# VCA_2.net
KiCad netlist of a schematic drawn in Altium Designer
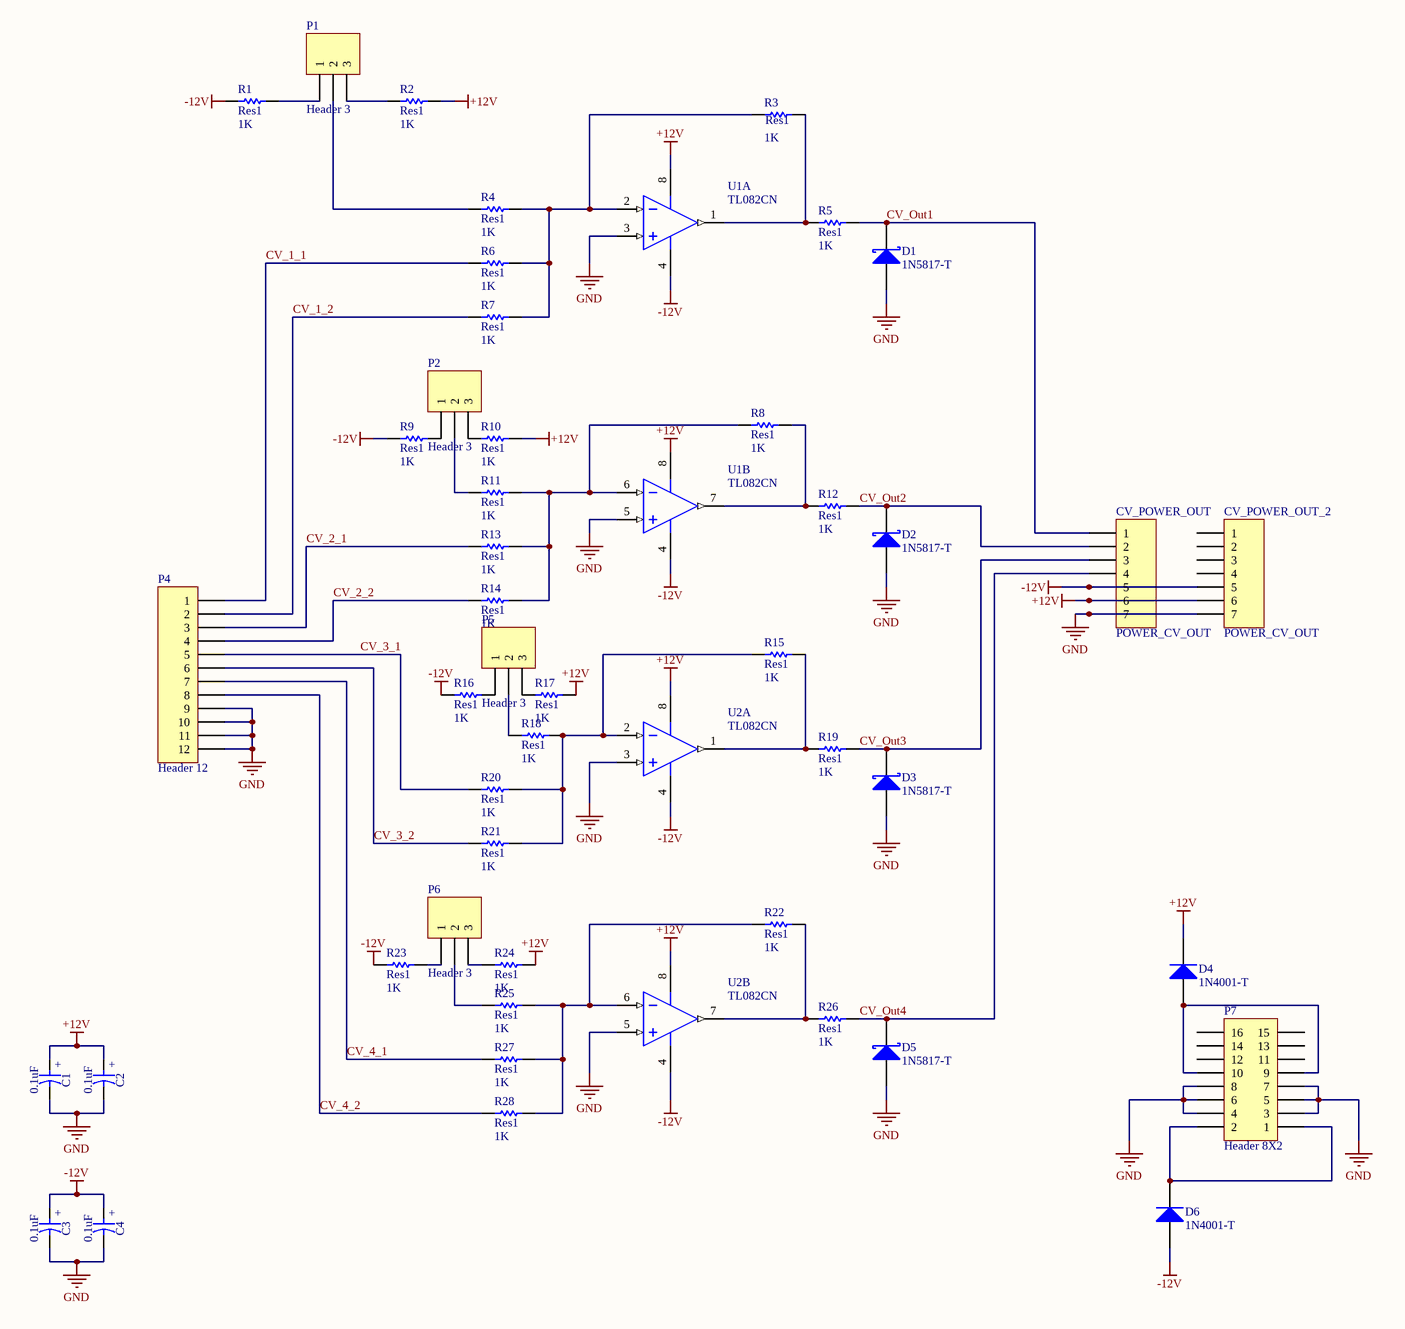
[diagram p0: VCA_2.SchDoc]

(export (version "E")
  (design (tool "Eeschema 10.0.6"))
  (components
    (comp (ref "C1")
      (value "0.1uF")
      (footprint "CAPPRB508-450x850")
      (description "Polarised capacitor")
      (fields
        (field (name "PART NUMBER") "CTEB_0.1UF_35V_10%_508-450X850")
        (field (name "VOLTAGE") "35V")
        (field (name "AUTHOR") "CERN DEM JLC")
      )
      (libsource (lib "Capacitors") (part "Capacitor - polarized"))
    )
    (comp (ref "C2")
      (value "0.1uF")
      (footprint "CAPPRB508-450x850")
      (description "Polarised capacitor")
      (fields
        (field (name "PART NUMBER") "CTEB_0.1UF_35V_10%_508-450X850")
        (field (name "VOLTAGE") "35V")
        (field (name "AUTHOR") "CERN DEM JLC")
      )
      (libsource (lib "Capacitors") (part "Capacitor - polarized"))
    )
    (comp (ref "C3")
      (value "0.1uF")
      (footprint "CAPPRB508-450x850")
      (description "Polarised capacitor")
      (fields
        (field (name "PART NUMBER") "CTEB_0.1UF_35V_10%_508-450X850")
        (field (name "VOLTAGE") "35V")
        (field (name "AUTHOR") "CERN DEM JLC")
      )
      (libsource (lib "Capacitors") (part "Capacitor - polarized"))
    )
    (comp (ref "C4")
      (value "0.1uF")
      (footprint "CAPPRB508-450x850")
      (description "Polarised capacitor")
      (fields
        (field (name "PART NUMBER") "CTEB_0.1UF_35V_10%_508-450X850")
        (field (name "VOLTAGE") "35V")
        (field (name "AUTHOR") "CERN DEM JLC")
      )
      (libsource (lib "Capacitors") (part "Capacitor - polarized"))
    )
    (comp (ref "CV_POWER_OUT")
      (value "POWER_CV_OUT")
      (footprint "HDR1X7")
      (description "Header, 7-Pin")
      (fields (field (name "PUBLISHER") "Altium Limited"))
      (libsource (lib "Miscellaneous Connectors") (part "Header 7"))
    )
    (comp (ref "CV_POWER_OUT_2")
      (value "POWER_CV_OUT")
      (footprint "HDR1X7")
      (description "Header, 7-Pin")
      (fields (field (name "PUBLISHER") "Altium Limited"))
      (libsource (lib "Miscellaneous Connectors") (part "Header 7"))
    )
    (comp (ref "D1")
      (value "1N5817-T")
      (footprint "DIOD-DO-41-P-2")
      (description "Schottky Barrier Rectifier, 1 A, 20 V, -65 to 125 degC, 2-Pin DO-41, RoHS, Tape and Reel")
      (fields (field (name "MANUFACTURER") "DiodesIncorporated"))
      (libsource (lib "Altium Content Vault") (part "DSKY-AK-2"))
    )
    (comp (ref "D2")
      (value "1N5817-T")
      (footprint "DIOD-DO-41-P-2")
      (description "Schottky Barrier Rectifier, 1 A, 20 V, -65 to 125 degC, 2-Pin DO-41, RoHS, Tape and Reel")
      (fields (field (name "MANUFACTURER") "DiodesIncorporated"))
      (libsource (lib "Altium Content Vault") (part "DSKY-AK-2"))
    )
    (comp (ref "D3")
      (value "1N5817-T")
      (footprint "DIOD-DO-41-P-2")
      (description "Schottky Barrier Rectifier, 1 A, 20 V, -65 to 125 degC, 2-Pin DO-41, RoHS, Tape and Reel")
      (fields (field (name "MANUFACTURER") "DiodesIncorporated"))
      (libsource (lib "Altium Content Vault") (part "DSKY-AK-2"))
    )
    (comp (ref "D4")
      (value "1N4001-T")
      (footprint "DIOD-DO-41-P-2_V")
      (description "1.0 A Rectifier, 15 pF, 50 V, -65 to 150 degC, 2-Pin DO-41 Plastic, RoHS, Tape and Reel")
      (fields (field (name "MANUFACTURER") "Diodes Inc"))
      (libsource (lib "Altium Content Vault") (part "DIOD-D-A1K2-2"))
    )
    (comp (ref "D5")
      (value "1N5817-T")
      (footprint "DIOD-DO-41-P-2")
      (description "Schottky Barrier Rectifier, 1 A, 20 V, -65 to 125 degC, 2-Pin DO-41, RoHS, Tape and Reel")
      (fields (field (name "MANUFACTURER") "DiodesIncorporated"))
      (libsource (lib "Altium Content Vault") (part "DSKY-AK-2"))
    )
    (comp (ref "D6")
      (value "1N4001-T")
      (footprint "DIOD-DO-41-P-2_V")
      (description "1.0 A Rectifier, 15 pF, 50 V, -65 to 150 degC, 2-Pin DO-41 Plastic, RoHS, Tape and Reel")
      (fields (field (name "MANUFACTURER") "Diodes Inc"))
      (libsource (lib "Altium Content Vault") (part "DIOD-D-A1K2-2"))
    )
    (comp (ref "P1")
      (value "Header 3")
      (footprint "HDR1X3")
      (description "Header, 3-Pin")
      (fields (field (name "PUBLISHER") "Altium Limited"))
      (libsource (lib "Miscellaneous Connectors") (part "Header 3"))
    )
    (comp (ref "P2")
      (value "Header 3")
      (footprint "HDR1X3")
      (description "Header, 3-Pin")
      (fields (field (name "PUBLISHER") "Altium Limited"))
      (libsource (lib "Miscellaneous Connectors") (part "Header 3"))
    )
    (comp (ref "P4")
      (value "Header 12")
      (footprint "HDR1X12")
      (description "Header, 12-Pin")
      (fields (field (name "PUBLISHER") "Altium Limited"))
      (libsource (lib "Miscellaneous Connectors") (part "Header 12"))
    )
    (comp (ref "P5")
      (value "Header 3")
      (footprint "HDR1X3")
      (description "Header, 3-Pin")
      (fields (field (name "PUBLISHER") "Altium Limited"))
      (libsource (lib "Miscellaneous Connectors") (part "Header 3"))
    )
    (comp (ref "P6")
      (value "Header 3")
      (footprint "HDR1X3")
      (description "Header, 3-Pin")
      (fields (field (name "PUBLISHER") "Altium Limited"))
      (libsource (lib "Miscellaneous Connectors") (part "Header 3"))
    )
    (comp (ref "P7")
      (value "Header 8X2")
      (footprint "HDR2X8")
      (description "Header, 8-Pin, Dual row")
      (fields (field (name "PUBLISHER") "Altium Limited"))
      (libsource (lib "Miscellaneous Connectors") (part "Header 8X2"))
    )
    (comp (ref "R1")
      (value "Res1")
      (footprint "AXIAL-0.3")
      (description "Resistor")
      (fields (field (name "ALTIUM_VALUE") "1K") (field (name "PUBLISHER") "Altium Limited"))
      (libsource (lib "Miscellaneous Devices") (part "Res1"))
    )
    (comp (ref "R2")
      (value "Res1")
      (footprint "AXIAL-0.3")
      (description "Resistor")
      (fields (field (name "ALTIUM_VALUE") "1K") (field (name "PUBLISHER") "Altium Limited"))
      (libsource (lib "Miscellaneous Devices") (part "Res1"))
    )
    (comp (ref "R3")
      (value "Res1")
      (footprint "AXIAL-0.3")
      (description "Resistor")
      (fields (field (name "ALTIUM_VALUE") "1K") (field (name "PUBLISHER") "Altium Limited"))
      (libsource (lib "Miscellaneous Devices") (part "Res1"))
    )
    (comp (ref "R4")
      (value "Res1")
      (footprint "AXIAL-0.3")
      (description "Resistor")
      (fields (field (name "ALTIUM_VALUE") "1K") (field (name "PUBLISHER") "Altium Limited"))
      (libsource (lib "Miscellaneous Devices") (part "Res1"))
    )
    (comp (ref "R5")
      (value "Res1")
      (footprint "AXIAL-0.3")
      (description "Resistor")
      (fields (field (name "ALTIUM_VALUE") "1K") (field (name "PUBLISHER") "Altium Limited"))
      (libsource (lib "Miscellaneous Devices") (part "Res1"))
    )
    (comp (ref "R6")
      (value "Res1")
      (footprint "AXIAL-0.3")
      (description "Resistor")
      (fields (field (name "ALTIUM_VALUE") "1K") (field (name "PUBLISHER") "Altium Limited"))
      (libsource (lib "Miscellaneous Devices") (part "Res1"))
    )
    (comp (ref "R7")
      (value "Res1")
      (footprint "AXIAL-0.3")
      (description "Resistor")
      (fields (field (name "ALTIUM_VALUE") "1K") (field (name "PUBLISHER") "Altium Limited"))
      (libsource (lib "Miscellaneous Devices") (part "Res1"))
    )
    (comp (ref "R8")
      (value "Res1")
      (footprint "AXIAL-0.3")
      (description "Resistor")
      (fields (field (name "ALTIUM_VALUE") "1K") (field (name "PUBLISHER") "Altium Limited"))
      (libsource (lib "Miscellaneous Devices") (part "Res1"))
    )
    (comp (ref "R9")
      (value "Res1")
      (footprint "AXIAL-0.3")
      (description "Resistor")
      (fields (field (name "ALTIUM_VALUE") "1K") (field (name "PUBLISHER") "Altium Limited"))
      (libsource (lib "Miscellaneous Devices") (part "Res1"))
    )
    (comp (ref "R10")
      (value "Res1")
      (footprint "AXIAL-0.3")
      (description "Resistor")
      (fields (field (name "ALTIUM_VALUE") "1K") (field (name "PUBLISHER") "Altium Limited"))
      (libsource (lib "Miscellaneous Devices") (part "Res1"))
    )
    (comp (ref "R11")
      (value "Res1")
      (footprint "AXIAL-0.3")
      (description "Resistor")
      (fields (field (name "ALTIUM_VALUE") "1K") (field (name "PUBLISHER") "Altium Limited"))
      (libsource (lib "Miscellaneous Devices") (part "Res1"))
    )
    (comp (ref "R12")
      (value "Res1")
      (footprint "AXIAL-0.3")
      (description "Resistor")
      (fields (field (name "ALTIUM_VALUE") "1K") (field (name "PUBLISHER") "Altium Limited"))
      (libsource (lib "Miscellaneous Devices") (part "Res1"))
    )
    (comp (ref "R13")
      (value "Res1")
      (footprint "AXIAL-0.3")
      (description "Resistor")
      (fields (field (name "ALTIUM_VALUE") "1K") (field (name "PUBLISHER") "Altium Limited"))
      (libsource (lib "Miscellaneous Devices") (part "Res1"))
    )
    (comp (ref "R14")
      (value "Res1")
      (footprint "AXIAL-0.3")
      (description "Resistor")
      (fields (field (name "ALTIUM_VALUE") "1K") (field (name "PUBLISHER") "Altium Limited"))
      (libsource (lib "Miscellaneous Devices") (part "Res1"))
    )
    (comp (ref "R15")
      (value "Res1")
      (footprint "AXIAL-0.3")
      (description "Resistor")
      (fields (field (name "ALTIUM_VALUE") "1K") (field (name "PUBLISHER") "Altium Limited"))
      (libsource (lib "Miscellaneous Devices") (part "Res1"))
    )
    (comp (ref "R16")
      (value "Res1")
      (footprint "AXIAL-0.3")
      (description "Resistor")
      (fields (field (name "ALTIUM_VALUE") "1K") (field (name "PUBLISHER") "Altium Limited"))
      (libsource (lib "Miscellaneous Devices") (part "Res1"))
    )
    (comp (ref "R17")
      (value "Res1")
      (footprint "AXIAL-0.3")
      (description "Resistor")
      (fields (field (name "ALTIUM_VALUE") "1K") (field (name "PUBLISHER") "Altium Limited"))
      (libsource (lib "Miscellaneous Devices") (part "Res1"))
    )
    (comp (ref "R18")
      (value "Res1")
      (footprint "AXIAL-0.3")
      (description "Resistor")
      (fields (field (name "ALTIUM_VALUE") "1K") (field (name "PUBLISHER") "Altium Limited"))
      (libsource (lib "Miscellaneous Devices") (part "Res1"))
    )
    (comp (ref "R19")
      (value "Res1")
      (footprint "AXIAL-0.3")
      (description "Resistor")
      (fields (field (name "ALTIUM_VALUE") "1K") (field (name "PUBLISHER") "Altium Limited"))
      (libsource (lib "Miscellaneous Devices") (part "Res1"))
    )
    (comp (ref "R20")
      (value "Res1")
      (footprint "AXIAL-0.3")
      (description "Resistor")
      (fields (field (name "ALTIUM_VALUE") "1K") (field (name "PUBLISHER") "Altium Limited"))
      (libsource (lib "Miscellaneous Devices") (part "Res1"))
    )
    (comp (ref "R21")
      (value "Res1")
      (footprint "AXIAL-0.3")
      (description "Resistor")
      (fields (field (name "ALTIUM_VALUE") "1K") (field (name "PUBLISHER") "Altium Limited"))
      (libsource (lib "Miscellaneous Devices") (part "Res1"))
    )
    (comp (ref "R22")
      (value "Res1")
      (footprint "AXIAL-0.3")
      (description "Resistor")
      (fields (field (name "ALTIUM_VALUE") "1K") (field (name "PUBLISHER") "Altium Limited"))
      (libsource (lib "Miscellaneous Devices") (part "Res1"))
    )
    (comp (ref "R23")
      (value "Res1")
      (footprint "AXIAL-0.3")
      (description "Resistor")
      (fields (field (name "ALTIUM_VALUE") "1K") (field (name "PUBLISHER") "Altium Limited"))
      (libsource (lib "Miscellaneous Devices") (part "Res1"))
    )
    (comp (ref "R24")
      (value "Res1")
      (footprint "AXIAL-0.3")
      (description "Resistor")
      (fields (field (name "ALTIUM_VALUE") "1K") (field (name "PUBLISHER") "Altium Limited"))
      (libsource (lib "Miscellaneous Devices") (part "Res1"))
    )
    (comp (ref "R25")
      (value "Res1")
      (footprint "AXIAL-0.3")
      (description "Resistor")
      (fields (field (name "ALTIUM_VALUE") "1K") (field (name "PUBLISHER") "Altium Limited"))
      (libsource (lib "Miscellaneous Devices") (part "Res1"))
    )
    (comp (ref "R26")
      (value "Res1")
      (footprint "AXIAL-0.3")
      (description "Resistor")
      (fields (field (name "ALTIUM_VALUE") "1K") (field (name "PUBLISHER") "Altium Limited"))
      (libsource (lib "Miscellaneous Devices") (part "Res1"))
    )
    (comp (ref "R27")
      (value "Res1")
      (footprint "AXIAL-0.3")
      (description "Resistor")
      (fields (field (name "ALTIUM_VALUE") "1K") (field (name "PUBLISHER") "Altium Limited"))
      (libsource (lib "Miscellaneous Devices") (part "Res1"))
    )
    (comp (ref "R28")
      (value "Res1")
      (footprint "AXIAL-0.3")
      (description "Resistor")
      (fields (field (name "ALTIUM_VALUE") "1K") (field (name "PUBLISHER") "Altium Limited"))
      (libsource (lib "Miscellaneous Devices") (part "Res1"))
    )
    (comp (ref "U1")
      (value "TL082CN")
      (footprint "STM-N8")
      (fields (field (name "MANUFACTURER") "STMicroelectronics"))
      (libsource (lib "Altium Content Vault") (part "STM-TL082-N8"))
    )
    (comp (ref "U2")
      (value "TL082CN")
      (footprint "STM-N8")
      (fields (field (name "MANUFACTURER") "STMicroelectronics"))
      (libsource (lib "Altium Content Vault") (part "STM-TL082-N8"))
    )
  )
  (nets
    (net (code "1") (name "+12V") (class "Default")
      (node (ref "C1") (pin "1") (pinfunction "1_1") (pintype "passive"))
      (node (ref "C2") (pin "1") (pinfunction "1_1") (pintype "passive"))
      (node (ref "CV_POWER_OUT") (pin "6") (pinfunction "6_6") (pintype "passive"))
      (node (ref "CV_POWER_OUT_2") (pin "6") (pinfunction "6_6") (pintype "passive"))
      (node (ref "D4") (pin "2") (pinfunction "K_2") (pintype "passive"))
      (node (ref "R10") (pin "2") (pinfunction "2_2") (pintype "passive"))
      (node (ref "R17") (pin "2") (pinfunction "2_2") (pintype "passive"))
      (node (ref "R2") (pin "2") (pinfunction "2_2") (pintype "passive"))
      (node (ref "R24") (pin "2") (pinfunction "2_2") (pintype "passive"))
      (node (ref "U1") (pin "8") (pinfunction "VCC+_8") (pintype "power_in"))
      (node (ref "U2") (pin "8") (pinfunction "VCC+_8") (pintype "power_in"))
    )
    (net (code "2") (name "-12V") (class "Default")
      (node (ref "C3") (pin "1") (pinfunction "1_1") (pintype "passive"))
      (node (ref "C4") (pin "1") (pinfunction "1_1") (pintype "passive"))
      (node (ref "CV_POWER_OUT") (pin "5") (pinfunction "5_5") (pintype "passive"))
      (node (ref "CV_POWER_OUT_2") (pin "5") (pinfunction "5_5") (pintype "passive"))
      (node (ref "D6") (pin "1") (pinfunction "A_1") (pintype "passive"))
      (node (ref "R1") (pin "1") (pinfunction "1_1") (pintype "passive"))
      (node (ref "R16") (pin "1") (pinfunction "1_1") (pintype "passive"))
      (node (ref "R23") (pin "1") (pinfunction "1_1") (pintype "passive"))
      (node (ref "R9") (pin "1") (pinfunction "1_1") (pintype "passive"))
      (node (ref "U1") (pin "4") (pinfunction "VCC-_4") (pintype "power_in"))
      (node (ref "U2") (pin "4") (pinfunction "VCC-_4") (pintype "power_in"))
    )
    (net (code "3") (name "/CV_1_1") (class "Default")
      (node (ref "P4") (pin "1") (pinfunction "1_1") (pintype "passive"))
      (node (ref "R6") (pin "1") (pinfunction "1_1") (pintype "passive"))
    )
    (net (code "4") (name "/CV_1_2") (class "Default")
      (node (ref "P4") (pin "2") (pinfunction "2_2") (pintype "passive"))
      (node (ref "R7") (pin "1") (pinfunction "1_1") (pintype "passive"))
    )
    (net (code "5") (name "/CV_2_1") (class "Default")
      (node (ref "P4") (pin "3") (pinfunction "3_3") (pintype "passive"))
      (node (ref "R13") (pin "1") (pinfunction "1_1") (pintype "passive"))
    )
    (net (code "6") (name "/CV_2_2") (class "Default")
      (node (ref "P4") (pin "4") (pinfunction "4_4") (pintype "passive"))
      (node (ref "R14") (pin "1") (pinfunction "1_1") (pintype "passive"))
    )
    (net (code "7") (name "/CV_3_1") (class "Default")
      (node (ref "P4") (pin "5") (pinfunction "5_5") (pintype "passive"))
      (node (ref "R20") (pin "1") (pinfunction "1_1") (pintype "passive"))
    )
    (net (code "8") (name "/CV_3_2") (class "Default")
      (node (ref "P4") (pin "6") (pinfunction "6_6") (pintype "passive"))
      (node (ref "R21") (pin "1") (pinfunction "1_1") (pintype "passive"))
    )
    (net (code "9") (name "/CV_4_1") (class "Default")
      (node (ref "P4") (pin "7") (pinfunction "7_7") (pintype "passive"))
      (node (ref "R27") (pin "1") (pinfunction "1_1") (pintype "passive"))
    )
    (net (code "10") (name "/CV_4_2") (class "Default")
      (node (ref "P4") (pin "8") (pinfunction "8_8") (pintype "passive"))
      (node (ref "R28") (pin "1") (pinfunction "1_1") (pintype "passive"))
    )
    (net (code "11") (name "/CV_Out1") (class "Default")
      (node (ref "CV_POWER_OUT") (pin "1") (pinfunction "1_1") (pintype "passive"))
      (node (ref "D1") (pin "2") (pinfunction "K_2") (pintype "passive"))
      (node (ref "R5") (pin "2") (pinfunction "2_2") (pintype "passive"))
    )
    (net (code "12") (name "/CV_Out2") (class "Default")
      (node (ref "CV_POWER_OUT") (pin "2") (pinfunction "2_2") (pintype "passive"))
      (node (ref "D2") (pin "2") (pinfunction "K_2") (pintype "passive"))
      (node (ref "R12") (pin "2") (pinfunction "2_2") (pintype "passive"))
    )
    (net (code "13") (name "/CV_Out3") (class "Default")
      (node (ref "CV_POWER_OUT") (pin "3") (pinfunction "3_3") (pintype "passive"))
      (node (ref "D3") (pin "2") (pinfunction "K_2") (pintype "passive"))
      (node (ref "R19") (pin "2") (pinfunction "2_2") (pintype "passive"))
    )
    (net (code "14") (name "/CV_Out4") (class "Default")
      (node (ref "CV_POWER_OUT") (pin "4") (pinfunction "4_4") (pintype "passive"))
      (node (ref "D5") (pin "2") (pinfunction "K_2") (pintype "passive"))
      (node (ref "R26") (pin "2") (pinfunction "2_2") (pintype "passive"))
    )
    (net (code "15") (name "GND") (class "Default")
      (node (ref "C1") (pin "2") (pinfunction "2_2") (pintype "passive"))
      (node (ref "C2") (pin "2") (pinfunction "2_2") (pintype "passive"))
      (node (ref "C3") (pin "2") (pinfunction "2_2") (pintype "passive"))
      (node (ref "C4") (pin "2") (pinfunction "2_2") (pintype "passive"))
      (node (ref "CV_POWER_OUT") (pin "7") (pinfunction "7_7") (pintype "passive"))
      (node (ref "CV_POWER_OUT_2") (pin "7") (pinfunction "7_7") (pintype "passive"))
      (node (ref "D1") (pin "1") (pinfunction "A_1") (pintype "passive"))
      (node (ref "D2") (pin "1") (pinfunction "A_1") (pintype "passive"))
      (node (ref "D3") (pin "1") (pinfunction "A_1") (pintype "passive"))
      (node (ref "D5") (pin "1") (pinfunction "A_1") (pintype "passive"))
      (node (ref "P4") (pin "10") (pinfunction "10_10") (pintype "passive"))
      (node (ref "P4") (pin "11") (pinfunction "11_11") (pintype "passive"))
      (node (ref "P4") (pin "12") (pinfunction "12_12") (pintype "passive"))
      (node (ref "P4") (pin "9") (pinfunction "9_9") (pintype "passive"))
      (node (ref "P7") (pin "3") (pinfunction "3_3") (pintype "passive"))
      (node (ref "P7") (pin "4") (pinfunction "4_4") (pintype "passive"))
      (node (ref "P7") (pin "5") (pinfunction "5_5") (pintype "passive"))
      (node (ref "P7") (pin "6") (pinfunction "6_6") (pintype "passive"))
      (node (ref "P7") (pin "7") (pinfunction "7_7") (pintype "passive"))
      (node (ref "P7") (pin "8") (pinfunction "8_8") (pintype "passive"))
      (node (ref "U1") (pin "3") (pinfunction "IN1+_3") (pintype "input"))
      (node (ref "U1") (pin "5") (pinfunction "IN2+_5") (pintype "input"))
      (node (ref "U2") (pin "3") (pinfunction "IN1+_3") (pintype "input"))
      (node (ref "U2") (pin "5") (pinfunction "IN2+_5") (pintype "input"))
    )
    (net (code "16") (name "Net-(D4-A)") (class "Default")
      (node (ref "D4") (pin "1") (pinfunction "A_1") (pintype "passive"))
      (node (ref "P7") (pin "10") (pinfunction "10_10") (pintype "passive"))
      (node (ref "P7") (pin "9") (pinfunction "9_9") (pintype "passive"))
    )
    (net (code "17") (name "Net-(D6-K)") (class "Default")
      (node (ref "D6") (pin "2") (pinfunction "K_2") (pintype "passive"))
      (node (ref "P7") (pin "1") (pinfunction "1_1") (pintype "passive"))
      (node (ref "P7") (pin "2") (pinfunction "2_2") (pintype "passive"))
    )
    (net (code "18") (name "Net-(P1-Pad1)") (class "Default")
      (node (ref "P1") (pin "1") (pinfunction "1_1") (pintype "passive"))
      (node (ref "R1") (pin "2") (pinfunction "2_2") (pintype "passive"))
    )
    (net (code "19") (name "Net-(P1-Pad2)") (class "Default")
      (node (ref "P1") (pin "2") (pinfunction "2_2") (pintype "passive"))
      (node (ref "R4") (pin "1") (pinfunction "1_1") (pintype "passive"))
    )
    (net (code "20") (name "Net-(P1-Pad3)") (class "Default")
      (node (ref "P1") (pin "3") (pinfunction "3_3") (pintype "passive"))
      (node (ref "R2") (pin "1") (pinfunction "1_1") (pintype "passive"))
    )
    (net (code "21") (name "Net-(P2-Pad1)") (class "Default")
      (node (ref "P2") (pin "1") (pinfunction "1_1") (pintype "passive"))
      (node (ref "R9") (pin "2") (pinfunction "2_2") (pintype "passive"))
    )
    (net (code "22") (name "Net-(P2-Pad2)") (class "Default")
      (node (ref "P2") (pin "2") (pinfunction "2_2") (pintype "passive"))
      (node (ref "R11") (pin "1") (pinfunction "1_1") (pintype "passive"))
    )
    (net (code "23") (name "Net-(P2-Pad3)") (class "Default")
      (node (ref "P2") (pin "3") (pinfunction "3_3") (pintype "passive"))
      (node (ref "R10") (pin "1") (pinfunction "1_1") (pintype "passive"))
    )
    (net (code "24") (name "Net-(P5-Pad1)") (class "Default")
      (node (ref "P5") (pin "1") (pinfunction "1_1") (pintype "passive"))
      (node (ref "R16") (pin "2") (pinfunction "2_2") (pintype "passive"))
    )
    (net (code "25") (name "Net-(P5-Pad2)") (class "Default")
      (node (ref "P5") (pin "2") (pinfunction "2_2") (pintype "passive"))
      (node (ref "R18") (pin "1") (pinfunction "1_1") (pintype "passive"))
    )
    (net (code "26") (name "Net-(P5-Pad3)") (class "Default")
      (node (ref "P5") (pin "3") (pinfunction "3_3") (pintype "passive"))
      (node (ref "R17") (pin "1") (pinfunction "1_1") (pintype "passive"))
    )
    (net (code "27") (name "Net-(P6-Pad1)") (class "Default")
      (node (ref "P6") (pin "1") (pinfunction "1_1") (pintype "passive"))
      (node (ref "R23") (pin "2") (pinfunction "2_2") (pintype "passive"))
    )
    (net (code "28") (name "Net-(P6-Pad2)") (class "Default")
      (node (ref "P6") (pin "2") (pinfunction "2_2") (pintype "passive"))
      (node (ref "R25") (pin "1") (pinfunction "1_1") (pintype "passive"))
    )
    (net (code "29") (name "Net-(P6-Pad3)") (class "Default")
      (node (ref "P6") (pin "3") (pinfunction "3_3") (pintype "passive"))
      (node (ref "R24") (pin "1") (pinfunction "1_1") (pintype "passive"))
    )
    (net (code "30") (name "Net-(U1A-IN1-)") (class "Default")
      (node (ref "R3") (pin "1") (pinfunction "1_1") (pintype "passive"))
      (node (ref "R4") (pin "2") (pinfunction "2_2") (pintype "passive"))
      (node (ref "R6") (pin "2") (pinfunction "2_2") (pintype "passive"))
      (node (ref "R7") (pin "2") (pinfunction "2_2") (pintype "passive"))
      (node (ref "U1") (pin "2") (pinfunction "IN1-_2") (pintype "input"))
    )
    (net (code "31") (name "Net-(U1A-OUT1)") (class "Default")
      (node (ref "R3") (pin "2") (pinfunction "2_2") (pintype "passive"))
      (node (ref "R5") (pin "1") (pinfunction "1_1") (pintype "passive"))
      (node (ref "U1") (pin "1") (pinfunction "OUT1_1") (pintype "output"))
    )
    (net (code "32") (name "Net-(U1B-IN2-)") (class "Default")
      (node (ref "R11") (pin "2") (pinfunction "2_2") (pintype "passive"))
      (node (ref "R13") (pin "2") (pinfunction "2_2") (pintype "passive"))
      (node (ref "R14") (pin "2") (pinfunction "2_2") (pintype "passive"))
      (node (ref "R8") (pin "1") (pinfunction "1_1") (pintype "passive"))
      (node (ref "U1") (pin "6") (pinfunction "IN2-_6") (pintype "input"))
    )
    (net (code "33") (name "Net-(U1B-OUT2)") (class "Default")
      (node (ref "R12") (pin "1") (pinfunction "1_1") (pintype "passive"))
      (node (ref "R8") (pin "2") (pinfunction "2_2") (pintype "passive"))
      (node (ref "U1") (pin "7") (pinfunction "OUT2_7") (pintype "output"))
    )
    (net (code "34") (name "Net-(U2A-IN1-)") (class "Default")
      (node (ref "R15") (pin "1") (pinfunction "1_1") (pintype "passive"))
      (node (ref "R18") (pin "2") (pinfunction "2_2") (pintype "passive"))
      (node (ref "R20") (pin "2") (pinfunction "2_2") (pintype "passive"))
      (node (ref "R21") (pin "2") (pinfunction "2_2") (pintype "passive"))
      (node (ref "U2") (pin "2") (pinfunction "IN1-_2") (pintype "input"))
    )
    (net (code "35") (name "Net-(U2A-OUT1)") (class "Default")
      (node (ref "R15") (pin "2") (pinfunction "2_2") (pintype "passive"))
      (node (ref "R19") (pin "1") (pinfunction "1_1") (pintype "passive"))
      (node (ref "U2") (pin "1") (pinfunction "OUT1_1") (pintype "output"))
    )
    (net (code "36") (name "Net-(U2B-IN2-)") (class "Default")
      (node (ref "R22") (pin "1") (pinfunction "1_1") (pintype "passive"))
      (node (ref "R25") (pin "2") (pinfunction "2_2") (pintype "passive"))
      (node (ref "R27") (pin "2") (pinfunction "2_2") (pintype "passive"))
      (node (ref "R28") (pin "2") (pinfunction "2_2") (pintype "passive"))
      (node (ref "U2") (pin "6") (pinfunction "IN2-_6") (pintype "input"))
    )
    (net (code "37") (name "Net-(U2B-OUT2)") (class "Default")
      (node (ref "R22") (pin "2") (pinfunction "2_2") (pintype "passive"))
      (node (ref "R26") (pin "1") (pinfunction "1_1") (pintype "passive"))
      (node (ref "U2") (pin "7") (pinfunction "OUT2_7") (pintype "output"))
    )
    (net (code "38") (name "unconnected-(CV_POWER_OUT_2-Pad1)") (class "Default")
      (node (ref "CV_POWER_OUT_2") (pin "1") (pinfunction "1_1") (pintype "passive"))
    )
    (net (code "39") (name "unconnected-(CV_POWER_OUT_2-Pad2)") (class "Default")
      (node (ref "CV_POWER_OUT_2") (pin "2") (pinfunction "2_2") (pintype "passive"))
    )
    (net (code "40") (name "unconnected-(CV_POWER_OUT_2-Pad3)") (class "Default")
      (node (ref "CV_POWER_OUT_2") (pin "3") (pinfunction "3_3") (pintype "passive"))
    )
    (net (code "41") (name "unconnected-(CV_POWER_OUT_2-Pad4)") (class "Default")
      (node (ref "CV_POWER_OUT_2") (pin "4") (pinfunction "4_4") (pintype "passive"))
    )
    (net (code "42") (name "unconnected-(P7-Pad11)") (class "Default")
      (node (ref "P7") (pin "11") (pinfunction "11_11") (pintype "passive"))
    )
    (net (code "43") (name "unconnected-(P7-Pad12)") (class "Default")
      (node (ref "P7") (pin "12") (pinfunction "12_12") (pintype "passive"))
    )
    (net (code "44") (name "unconnected-(P7-Pad13)") (class "Default")
      (node (ref "P7") (pin "13") (pinfunction "13_13") (pintype "passive"))
    )
    (net (code "45") (name "unconnected-(P7-Pad14)") (class "Default")
      (node (ref "P7") (pin "14") (pinfunction "14_14") (pintype "passive"))
    )
    (net (code "46") (name "unconnected-(P7-Pad15)") (class "Default")
      (node (ref "P7") (pin "15") (pinfunction "15_15") (pintype "passive"))
    )
    (net (code "47") (name "unconnected-(P7-Pad16)") (class "Default")
      (node (ref "P7") (pin "16") (pinfunction "16_16") (pintype "passive"))
    )
  )
)
